# Headphone.net
KiCad netlist of a schematic drawn in Altium Designer
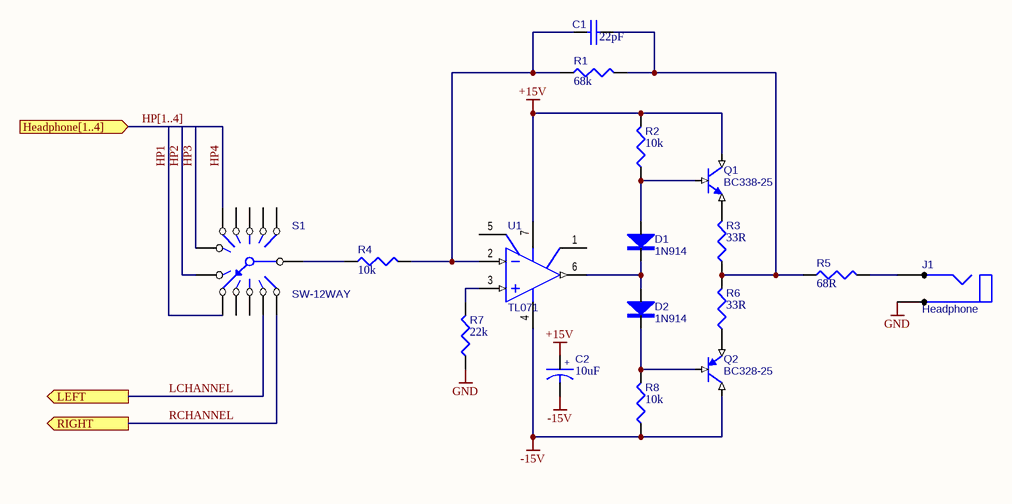
[diagram p0: Headphone.SchDoc]

(export (version "E")
  (design (tool "Eeschema 10.0.6"))
  (components
    (comp (ref "C1")
      (value "22pF")
      (footprint "RAD0.2")
      (description "Capacitor")
      (libsource (lib "*") (part "CAP"))
    )
    (comp (ref "C2")
      (value "10uF")
      (footprint "RB.2/.4")
      (description "Bi-Polar Capacitor")
      (libsource (lib "*") (part "CAPACITOR POL"))
    )
    (comp (ref "D1")
      (value "1N914")
      (footprint "DIODE0.4")
      (description "Diode")
      (libsource (lib "*") (part "1N914"))
    )
    (comp (ref "D2")
      (value "1N914")
      (footprint "DIODE0.4")
      (description "Diode")
      (libsource (lib "*") (part "1N914"))
    )
    (comp (ref "J1")
      (value "Headphone")
      (footprint "JACK-6.25MM")
      (libsource (lib "*") (part "PHONEJACK MONO"))
    )
    (comp (ref "Q1")
      (value "BC338-25")
      (footprint "TO-92A")
      (description "NPN BJT")
      (libsource (lib "*") (part "BC338-25"))
    )
    (comp (ref "Q2")
      (value "BC328-25")
      (footprint "TO-92A")
      (description "PNP BJT")
      (libsource (lib "*") (part "BC328-25"))
    )
    (comp (ref "R1")
      (value "68k")
      (footprint "AXIAL0.4")
      (description "Resistor")
      (libsource (lib "") (part "RES1_1"))
    )
    (comp (ref "R2")
      (value "10k")
      (footprint "AXIAL0.4")
      (description "Resistor")
      (libsource (lib "*") (part "RES1"))
    )
    (comp (ref "R3")
      (value "33R")
      (footprint "AXIAL0.4")
      (description "Resistor")
      (libsource (lib "*") (part "RES1"))
    )
    (comp (ref "R4")
      (value "10k")
      (footprint "AXIAL0.4")
      (description "Resistor")
      (libsource (lib "") (part "RES1_1"))
    )
    (comp (ref "R5")
      (value "68R")
      (footprint "AXIAL0.4")
      (description "Resistor")
      (libsource (lib "") (part "RES1_1"))
    )
    (comp (ref "R6")
      (value "33R")
      (footprint "AXIAL0.4")
      (description "Resistor")
      (libsource (lib "*") (part "RES1"))
    )
    (comp (ref "R7")
      (value "22k")
      (footprint "AXIAL0.4")
      (description "Resistor")
      (libsource (lib "*") (part "RES1"))
    )
    (comp (ref "R8")
      (value "10k")
      (footprint "AXIAL0.4")
      (description "Resistor")
      (libsource (lib "*") (part "RES1"))
    )
    (comp (ref "S1") (value "SW-12WAY") (footprint "SW-12WAY") (libsource (lib "*") (part "SW-12WAY")))
    (comp (ref "U1")
      (value "TL071")
      (footprint "DIP8")
      (description "Low-Noise  JFET-Input Operational Amplifiers")
      (libsource (lib "*") (part "TL071"))
    )
  )
  (nets
    (net (code "1") (name "+15V") (class "Default")
      (node (ref "C2") (pin "1") (pinfunction "1_1") (pintype "passive"))
      (node (ref "Q1") (pin "1") (pinfunction "C_1") (pintype "input"))
      (node (ref "R2") (pin "2") (pinfunction "2_2") (pintype "passive"))
      (node (ref "U1") (pin "7") (pinfunction "VCC+_7") (pintype "power_in"))
    )
    (net (code "2") (name "-15V") (class "Default")
      (node (ref "C2") (pin "2") (pinfunction "2_2") (pintype "passive"))
      (node (ref "Q2") (pin "1") (pinfunction "C_1") (pintype "input"))
      (node (ref "R8") (pin "1") (pinfunction "1_1") (pintype "passive"))
      (node (ref "U1") (pin "4") (pinfunction "VCC-_4") (pintype "power_in"))
    )
    (net (code "3") (name "/HP1") (class "Default")
      (node (ref "S1") (pin "8") (pinfunction "8_8") (pintype "passive"))
    )
    (net (code "4") (name "/HP2") (class "Default")
      (node (ref "S1") (pin "7") (pinfunction "7_7") (pintype "passive"))
    )
    (net (code "5") (name "/HP3") (class "Default")
      (node (ref "S1") (pin "6") (pinfunction "6_6") (pintype "passive"))
    )
    (net (code "6") (name "/HP4") (class "Default")
      (node (ref "S1") (pin "5") (pinfunction "5_5") (pintype "passive"))
    )
    (net (code "8") (name "/LCHANNEL") (class "Default")
      (node (ref "S1") (pin "11") (pinfunction "11_11") (pintype "passive"))
    )
    (net (code "9") (name "/RCHANNEL") (class "Default")
      (node (ref "S1") (pin "12") (pinfunction "12_12") (pintype "passive"))
    )
    (net (code "10") (name "GND") (class "Default")
      (node (ref "J1") (pin "3") (pinfunction "C_3") (pintype "passive"))
      (node (ref "R7") (pin "1") (pinfunction "1_1") (pintype "passive"))
    )
    (net (code "11") (name "Net-(C1-Pad2)") (class "Default")
      (node (ref "C1") (pin "2") (pinfunction "2_2") (pintype "passive"))
      (node (ref "R1") (pin "2") (pinfunction "2_2") (pintype "passive"))
      (node (ref "R3") (pin "1") (pinfunction "1_1") (pintype "passive"))
      (node (ref "R5") (pin "1") (pinfunction "1_1") (pintype "passive"))
      (node (ref "R6") (pin "2") (pinfunction "2_2") (pintype "passive"))
    )
    (net (code "12") (name "Net-(D1-A)") (class "Default")
      (node (ref "D1") (pin "1") (pinfunction "A_1") (pintype "passive"))
      (node (ref "Q1") (pin "2") (pinfunction "B_2") (pintype "input"))
      (node (ref "R2") (pin "1") (pinfunction "1_1") (pintype "passive"))
    )
    (net (code "13") (name "Net-(D1-K)") (class "Default")
      (node (ref "D1") (pin "2") (pinfunction "K_2") (pintype "passive"))
      (node (ref "D2") (pin "1") (pinfunction "A_1") (pintype "passive"))
      (node (ref "U1") (pin "6") (pinfunction "OUT_6") (pintype "output"))
    )
    (net (code "14") (name "Net-(D2-K)") (class "Default")
      (node (ref "D2") (pin "2") (pinfunction "K_2") (pintype "passive"))
      (node (ref "Q2") (pin "2") (pinfunction "B_2") (pintype "input"))
      (node (ref "R8") (pin "2") (pinfunction "2_2") (pintype "passive"))
    )
    (net (code "15") (name "Net-(J1-A)") (class "Default")
      (node (ref "J1") (pin "1") (pinfunction "A_1") (pintype "passive"))
      (node (ref "R5") (pin "2") (pinfunction "2_2") (pintype "passive"))
    )
    (net (code "16") (name "Net-(Q1-E)") (class "Default")
      (node (ref "Q1") (pin "3") (pinfunction "E_3") (pintype "input"))
      (node (ref "R3") (pin "2") (pinfunction "2_2") (pintype "passive"))
    )
    (net (code "17") (name "Net-(Q2-E)") (class "Default")
      (node (ref "Q2") (pin "3") (pinfunction "E_3") (pintype "input"))
      (node (ref "R6") (pin "1") (pinfunction "1_1") (pintype "passive"))
    )
    (net (code "18") (name "Net-(R4-Pad1)") (class "Default")
      (node (ref "R4") (pin "1") (pinfunction "1_1") (pintype "passive"))
      (node (ref "S1") (pin "13") (pinfunction "13_13") (pintype "passive"))
    )
    (net (code "19") (name "Net-(U1-IN+)") (class "Default")
      (node (ref "R7") (pin "2") (pinfunction "2_2") (pintype "passive"))
      (node (ref "U1") (pin "3") (pinfunction "IN+_3") (pintype "input"))
    )
    (net (code "20") (name "Net-(U1-IN-)") (class "Default")
      (node (ref "C1") (pin "1") (pinfunction "1_1") (pintype "passive"))
      (node (ref "R1") (pin "1") (pinfunction "1_1") (pintype "passive"))
      (node (ref "R4") (pin "2") (pinfunction "2_2") (pintype "passive"))
      (node (ref "U1") (pin "2") (pinfunction "IN-_2") (pintype "input"))
    )
    (net (code "21") (name "unconnected-(S1-Pad1)") (class "Default")
      (node (ref "S1") (pin "1") (pinfunction "1_1") (pintype "passive"))
    )
    (net (code "22") (name "unconnected-(S1-Pad2)") (class "Default")
      (node (ref "S1") (pin "2") (pinfunction "2_2") (pintype "passive"))
    )
    (net (code "23") (name "unconnected-(S1-Pad3)") (class "Default")
      (node (ref "S1") (pin "3") (pinfunction "3_3") (pintype "passive"))
    )
    (net (code "24") (name "unconnected-(S1-Pad4)") (class "Default")
      (node (ref "S1") (pin "4") (pinfunction "4_4") (pintype "passive"))
    )
    (net (code "25") (name "unconnected-(S1-Pad9)") (class "Default")
      (node (ref "S1") (pin "9") (pinfunction "9_9") (pintype "passive"))
    )
    (net (code "26") (name "unconnected-(S1-Pad10)") (class "Default")
      (node (ref "S1") (pin "10") (pinfunction "10_10") (pintype "passive"))
    )
    (net (code "27") (name "unconnected-(U1-N1{slash}O.S.-Pad1)") (class "Default")
      (node (ref "U1") (pin "1") (pinfunction "N1/O.S._1") (pintype "passive"))
    )
    (net (code "28") (name "unconnected-(U1-O.S._N2-Pad5)") (class "Default")
      (node (ref "U1") (pin "5") (pinfunction "O.S._N2_5") (pintype "passive"))
    )
  )
)
